# Schematic_Scout2Map_JSON.net
KiCad netlist of a schematic drawn in EasyEDA
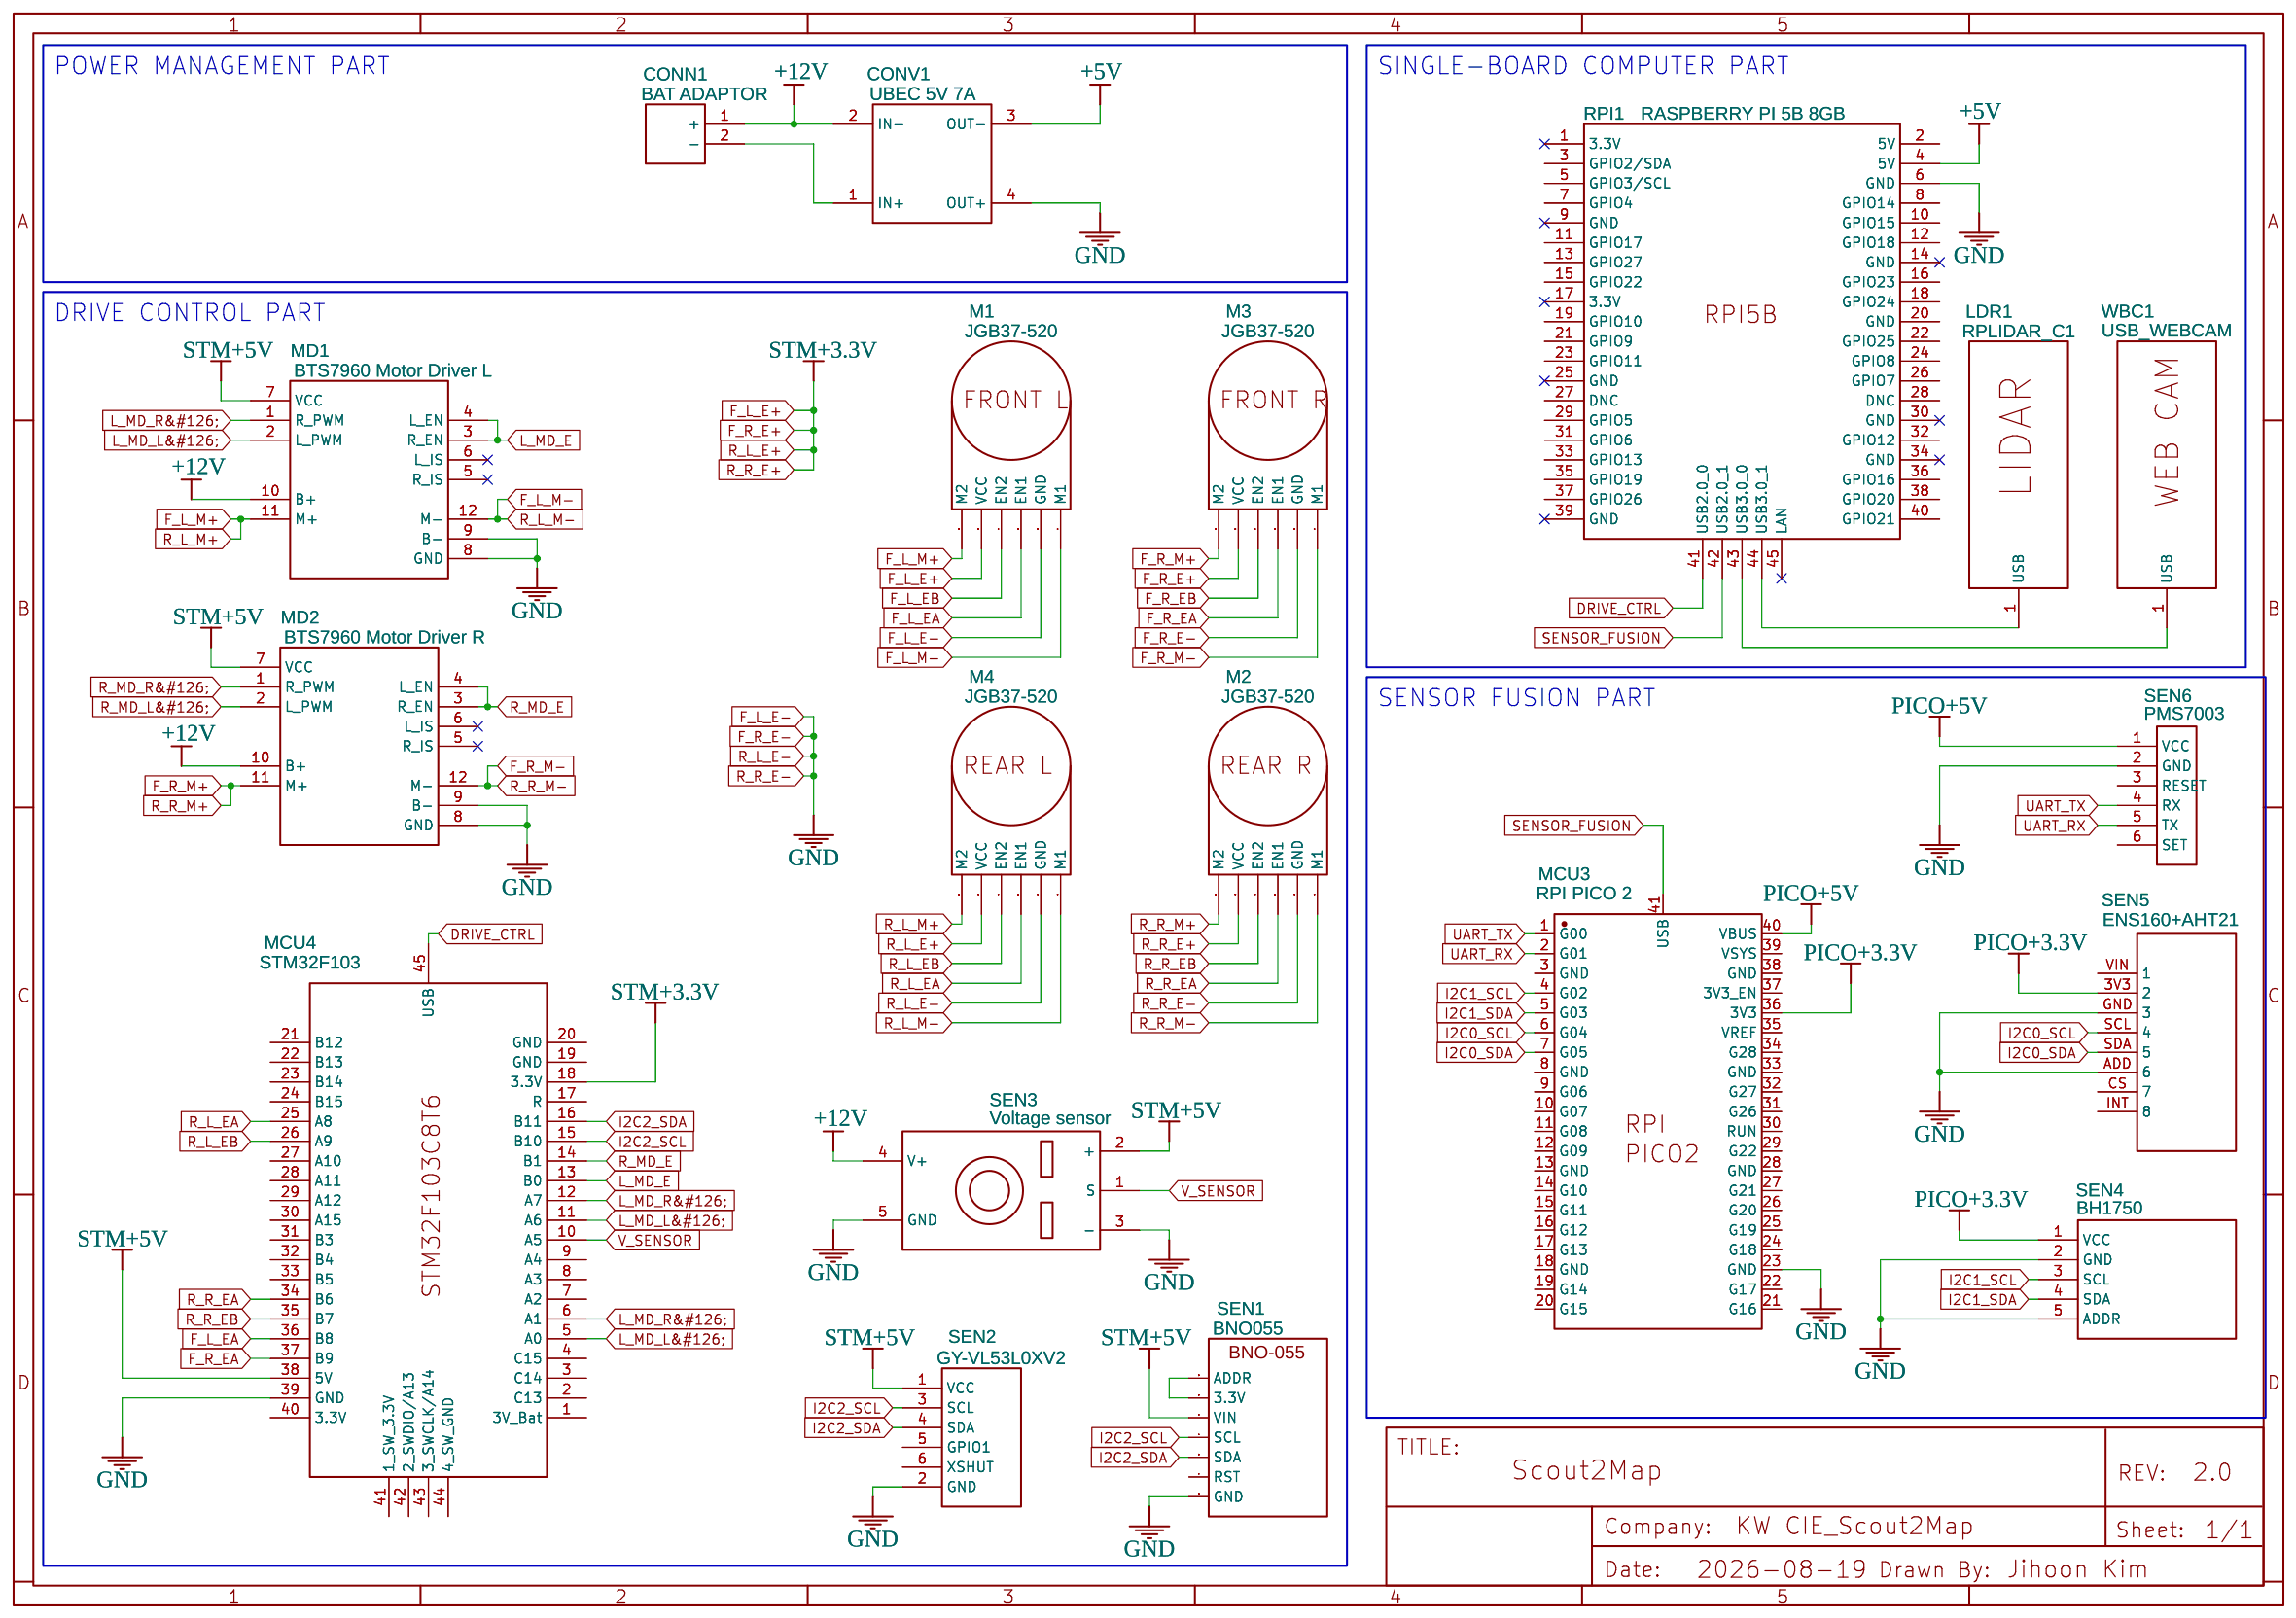
[diagram p0: schematic sheet]

(export (version "E")
  (design (tool "Eeschema 10.0.6"))
  (components
    (comp (ref "CONN1") (value "BAT ADAPTOR") (libsource (lib "") (part "Ac Adaptor")))
    (comp (ref "CONV1") (value "UBEC 5V 7A") (libsource (lib "") (part "Stepdown")))
    (comp (ref "LDR1") (value "RPLIDAR_C1") (libsource (lib "") (part "TFMini_Plus_Lidar_1")))
    (comp (ref "M1") (value "JGB37-520") (libsource (lib "") (part "N20_with_ENCODER_1")))
    (comp (ref "M2") (value "JGB37-520") (libsource (lib "") (part "N20_with_ENCODER_3")))
    (comp (ref "M3") (value "JGB37-520") (libsource (lib "") (part "N20_with_ENCODER")))
    (comp (ref "M4") (value "JGB37-520") (libsource (lib "") (part "N20_with_ENCODER_2")))
    (comp (ref "MCU3")
      (value "RPI PICO 2")
      (fields (field (name "Manufacturer Part") "SC0918") (field (name "Manufacturer") "Raspberry Pi"))
      (libsource (lib "") (part "RaspberryPi_Pico2 + USB"))
    )
    (comp (ref "MCU4")
      (value "STM32F103")
      (fields (field (name "Manufacturer Part") "STM32F103C8T6"))
      (libsource (lib "") (part "STM32F103C8T6 + USB"))
    )
    (comp (ref "MD1") (value "BTS7960 Motor Driver L") (libsource (lib "") (part "BST7960 Motor Drover")))
    (comp (ref "MD2") (value "BTS7960 Motor Driver R") (libsource (lib "") (part "BST7960 Motor Drover")))
    (comp (ref "RPI1")
      (value "RASPBERRY PI 5B 8GB")
      (fields
        (field (name "Manufacturer Part") "Raspberry Pi 4 Model B")
        (field (name "Manufacturer") "Raspberry Pi")
      )
      (libsource (lib "") (part "RASPBERRY PI 4B + USB"))
    )
    (comp (ref "SEN1") (value "BNO055") (libsource (lib "") (part "BNO055")))
    (comp (ref "SEN2") (value "GY-VL53L0XV2") (libsource (lib "") (part "GY-VL53L0XV2")))
    (comp (ref "SEN3") (value "Voltage sensor") (libsource (lib "") (part "Voltage sensor")))
    (comp (ref "SEN4") (value "BH1750") (libsource (lib "") (part "BH1750")))
    (comp (ref "SEN5") (value "ENS160+AHT21") (libsource (lib "") (part "ENS160+AHT21")))
    (comp (ref "SEN6") (value "PMS7003") (libsource (lib "") (part "Plantower PMS7003")))
    (comp (ref "WBC1") (value "USB_WEBCAM") (libsource (lib "") (part "TFMini_Plus_Lidar")))
  )
  (nets
    (net (code "1") (name "+5V") (class "Default")
      (node (ref "CONV1") (pin "3") (pinfunction "OUT-_3") (pintype "unspecified"))
      (node (ref "RPI1") (pin "4") (pinfunction "5V_4") (pintype "passive"))
    )
    (net (code "2") (name "+12V") (class "Default")
      (node (ref "CONN1") (pin "1") (pinfunction "+_1") (pintype "unspecified"))
      (node (ref "CONV1") (pin "2") (pinfunction "IN-_2") (pintype "unspecified"))
      (node (ref "MD1") (pin "10") (pinfunction "B+_10") (pintype "unspecified"))
      (node (ref "MD2") (pin "10") (pinfunction "B+_10") (pintype "unspecified"))
      (node (ref "SEN3") (pin "4") (pinfunction "V+_4") (pintype "unspecified"))
    )
    (net (code "3") (name "DRIVE_CTRL") (class "Default")
      (node (ref "MCU4") (pin "45") (pinfunction "USB_45") (pintype "unspecified"))
      (node (ref "RPI1") (pin "41") (pinfunction "USB2.0_0_41") (pintype "bidirectional"))
    )
    (net (code "4") (name "F_L_E+") (class "Default")
      (node (ref "M1") (pin "5") (pinfunction "VCC_5") (pintype "unspecified"))
      (node (ref "M2") (pin "5") (pinfunction "VCC_5") (pintype "unspecified"))
      (node (ref "M3") (pin "5") (pinfunction "VCC_5") (pintype "unspecified"))
      (node (ref "M4") (pin "5") (pinfunction "VCC_5") (pintype "unspecified"))
      (node (ref "MCU4") (pin "18") (pinfunction "3.3V_18") (pintype "unspecified"))
    )
    (net (code "5") (name "F_L_E-") (class "Default")
      (node (ref "CONV1") (pin "4") (pinfunction "OUT+_4") (pintype "unspecified"))
      (node (ref "M1") (pin "2") (pinfunction "GND_2") (pintype "unspecified"))
      (node (ref "M2") (pin "2") (pinfunction "GND_2") (pintype "unspecified"))
      (node (ref "M3") (pin "2") (pinfunction "GND_2") (pintype "unspecified"))
      (node (ref "M4") (pin "2") (pinfunction "GND_2") (pintype "unspecified"))
      (node (ref "MCU3") (pin "23") (pinfunction "GND_23") (pintype "unspecified"))
      (node (ref "MCU4") (pin "39") (pinfunction "GND_39") (pintype "unspecified"))
      (node (ref "MD1") (pin "8") (pinfunction "GND_8") (pintype "unspecified"))
      (node (ref "MD1") (pin "9") (pinfunction "B-_9") (pintype "unspecified"))
      (node (ref "MD2") (pin "8") (pinfunction "GND_8") (pintype "unspecified"))
      (node (ref "MD2") (pin "9") (pinfunction "B-_9") (pintype "unspecified"))
      (node (ref "RPI1") (pin "6") (pinfunction "GND_6") (pintype "unspecified"))
      (node (ref "SEN1") (pin "3") (pinfunction "GND_3") (pintype "unspecified"))
      (node (ref "SEN2") (pin "2") (pinfunction "GND_2") (pintype "unspecified"))
      (node (ref "SEN3") (pin "3") (pinfunction "-_3") (pintype "unspecified"))
      (node (ref "SEN3") (pin "5") (pinfunction "GND_5") (pintype "unspecified"))
      (node (ref "SEN4") (pin "2") (pinfunction "GND_2") (pintype "unspecified"))
      (node (ref "SEN4") (pin "5") (pinfunction "ADDR_5") (pintype "unspecified"))
      (node (ref "SEN5") (pin "ADD") (pinfunction "6_ADD") (pintype "unspecified"))
      (node (ref "SEN5") (pin "GND") (pinfunction "3_GND") (pintype "unspecified"))
      (node (ref "SEN6") (pin "2") (pinfunction "GND_2") (pintype "unspecified"))
    )
    (net (code "6") (name "F_L_EA") (class "Default")
      (node (ref "M1") (pin "3") (pinfunction "EN1_3") (pintype "unspecified"))
      (node (ref "MCU4") (pin "36") (pinfunction "B8_36") (pintype "unspecified"))
    )
    (net (code "7") (name "F_L_EB") (class "Default")
      (node (ref "M1") (pin "4") (pinfunction "EN2_4") (pintype "unspecified"))
    )
    (net (code "8") (name "F_L_M+") (class "Default")
      (node (ref "M1") (pin "6") (pinfunction "M2_6") (pintype "unspecified"))
      (node (ref "M4") (pin "6") (pinfunction "M2_6") (pintype "unspecified"))
      (node (ref "MD1") (pin "11") (pinfunction "M+_11") (pintype "unspecified"))
    )
    (net (code "9") (name "F_L_M-") (class "Default")
      (node (ref "M1") (pin "1") (pinfunction "M1_1") (pintype "unspecified"))
      (node (ref "M4") (pin "1") (pinfunction "M1_1") (pintype "unspecified"))
      (node (ref "MD1") (pin "12") (pinfunction "M-_12") (pintype "unspecified"))
    )
    (net (code "10") (name "F_R_EA") (class "Default")
      (node (ref "M3") (pin "3") (pinfunction "EN1_3") (pintype "unspecified"))
      (node (ref "MCU4") (pin "37") (pinfunction "B9_37") (pintype "unspecified"))
    )
    (net (code "11") (name "F_R_EB") (class "Default")
      (node (ref "M3") (pin "4") (pinfunction "EN2_4") (pintype "unspecified"))
    )
    (net (code "12") (name "F_R_M+") (class "Default")
      (node (ref "M2") (pin "6") (pinfunction "M2_6") (pintype "unspecified"))
      (node (ref "M3") (pin "6") (pinfunction "M2_6") (pintype "unspecified"))
      (node (ref "MD2") (pin "11") (pinfunction "M+_11") (pintype "unspecified"))
    )
    (net (code "13") (name "F_R_M-") (class "Default")
      (node (ref "M2") (pin "1") (pinfunction "M1_1") (pintype "unspecified"))
      (node (ref "M3") (pin "1") (pinfunction "M1_1") (pintype "unspecified"))
      (node (ref "MD2") (pin "12") (pinfunction "M-_12") (pintype "unspecified"))
    )
    (net (code "14") (name "I2C0_SCL") (class "Default")
      (node (ref "MCU3") (pin "6") (pinfunction "G04_6") (pintype "unspecified"))
      (node (ref "SEN5") (pin "SCL") (pinfunction "4_SCL") (pintype "unspecified"))
    )
    (net (code "15") (name "I2C0_SDA") (class "Default")
      (node (ref "MCU3") (pin "7") (pinfunction "G05_7") (pintype "unspecified"))
      (node (ref "SEN5") (pin "SDA") (pinfunction "5_SDA") (pintype "unspecified"))
    )
    (net (code "16") (name "I2C1_SCL") (class "Default")
      (node (ref "MCU3") (pin "4") (pinfunction "G02_4") (pintype "unspecified"))
      (node (ref "SEN4") (pin "3") (pinfunction "SCL_3") (pintype "unspecified"))
    )
    (net (code "17") (name "I2C1_SDA") (class "Default")
      (node (ref "MCU3") (pin "5") (pinfunction "G03_5") (pintype "unspecified"))
      (node (ref "SEN4") (pin "4") (pinfunction "SDA_4") (pintype "unspecified"))
    )
    (net (code "18") (name "I2C2_SCL") (class "Default")
      (node (ref "MCU4") (pin "15") (pinfunction "B10_15") (pintype "unspecified"))
      (node (ref "SEN1") (pin "4") (pinfunction "SCL_4") (pintype "unspecified"))
      (node (ref "SEN2") (pin "3") (pinfunction "SCL_3") (pintype "unspecified"))
    )
    (net (code "19") (name "I2C2_SDA") (class "Default")
      (node (ref "MCU4") (pin "16") (pinfunction "B11_16") (pintype "unspecified"))
      (node (ref "SEN1") (pin "5") (pinfunction "SDA_5") (pintype "unspecified"))
      (node (ref "SEN2") (pin "4") (pinfunction "SDA_4") (pintype "unspecified"))
    )
    (net (code "20") (name "L_MD_E") (class "Default")
      (node (ref "MCU4") (pin "13") (pinfunction "B0_13") (pintype "unspecified"))
      (node (ref "MD1") (pin "3") (pinfunction "R_EN_3") (pintype "unspecified"))
      (node (ref "MD1") (pin "4") (pinfunction "L_EN_4") (pintype "unspecified"))
    )
    (net (code "21") (name "L_MD_L&#126;") (class "Default")
      (node (ref "MCU4") (pin "11") (pinfunction "A6_11") (pintype "unspecified"))
      (node (ref "MCU4") (pin "5") (pinfunction "A0_5") (pintype "unspecified"))
      (node (ref "MD1") (pin "2") (pinfunction "L_PWM_2") (pintype "unspecified"))
    )
    (net (code "22") (name "L_MD_R&#126;") (class "Default")
      (node (ref "MCU4") (pin "12") (pinfunction "A7_12") (pintype "unspecified"))
      (node (ref "MCU4") (pin "6") (pinfunction "A1_6") (pintype "unspecified"))
      (node (ref "MD1") (pin "1") (pinfunction "R_PWM_1") (pintype "unspecified"))
    )
    (net (code "23") (name "Net-(CONN1--)") (class "Default")
      (node (ref "CONN1") (pin "2") (pinfunction "-_2") (pintype "unspecified"))
      (node (ref "CONV1") (pin "1") (pinfunction "IN+_1") (pintype "unspecified"))
    )
    (net (code "24") (name "Net-(LDR1-USB)") (class "Default")
      (node (ref "LDR1") (pin "1") (pinfunction "USB_1") (pintype "unspecified"))
      (node (ref "RPI1") (pin "44") (pinfunction "USB3.0_1_44") (pintype "bidirectional"))
    )
    (net (code "25") (name "Net-(RPI1-USB3.0_0)") (class "Default")
      (node (ref "RPI1") (pin "43") (pinfunction "USB3.0_0_43") (pintype "bidirectional"))
      (node (ref "WBC1") (pin "1") (pinfunction "USB_1") (pintype "unspecified"))
    )
    (net (code "26") (name "Net-(SEN1-3.3V)") (class "Default")
      (node (ref "SEN1") (pin "2") (pinfunction "3.3V_2") (pintype "unspecified"))
      (node (ref "SEN1") (pin "6") (pinfunction "ADDR_6") (pintype "unspecified"))
    )
    (net (code "27") (name "PICO+3.3V") (class "Default")
      (node (ref "MCU3") (pin "36") (pinfunction "3V3_36") (pintype "unspecified"))
      (node (ref "SEN4") (pin "1") (pinfunction "VCC_1") (pintype "unspecified"))
      (node (ref "SEN5") (pin "3V3") (pinfunction "2_3V3") (pintype "unspecified"))
    )
    (net (code "28") (name "PICO+5V") (class "Default")
      (node (ref "MCU3") (pin "40") (pinfunction "VBUS_40") (pintype "unspecified"))
      (node (ref "SEN6") (pin "1") (pinfunction "VCC_1") (pintype "unspecified"))
    )
    (net (code "29") (name "R_L_EA") (class "Default")
      (node (ref "M4") (pin "3") (pinfunction "EN1_3") (pintype "unspecified"))
      (node (ref "MCU4") (pin "25") (pinfunction "A8_25") (pintype "unspecified"))
    )
    (net (code "30") (name "R_L_EB") (class "Default")
      (node (ref "M4") (pin "4") (pinfunction "EN2_4") (pintype "unspecified"))
      (node (ref "MCU4") (pin "26") (pinfunction "A9_26") (pintype "unspecified"))
    )
    (net (code "31") (name "R_MD_E") (class "Default")
      (node (ref "MCU4") (pin "14") (pinfunction "B1_14") (pintype "unspecified"))
      (node (ref "MD2") (pin "3") (pinfunction "R_EN_3") (pintype "unspecified"))
      (node (ref "MD2") (pin "4") (pinfunction "L_EN_4") (pintype "unspecified"))
    )
    (net (code "32") (name "R_MD_L&#126;") (class "Default")
      (node (ref "MD2") (pin "2") (pinfunction "L_PWM_2") (pintype "unspecified"))
    )
    (net (code "33") (name "R_MD_R&#126;") (class "Default")
      (node (ref "MD2") (pin "1") (pinfunction "R_PWM_1") (pintype "unspecified"))
    )
    (net (code "34") (name "R_R_EA") (class "Default")
      (node (ref "M2") (pin "3") (pinfunction "EN1_3") (pintype "unspecified"))
      (node (ref "MCU4") (pin "34") (pinfunction "B6_34") (pintype "unspecified"))
    )
    (net (code "35") (name "R_R_EB") (class "Default")
      (node (ref "M2") (pin "4") (pinfunction "EN2_4") (pintype "unspecified"))
      (node (ref "MCU4") (pin "35") (pinfunction "B7_35") (pintype "unspecified"))
    )
    (net (code "36") (name "SENSOR_FUSION") (class "Default")
      (node (ref "MCU3") (pin "41") (pinfunction "USB_41") (pintype "unspecified"))
      (node (ref "RPI1") (pin "42") (pinfunction "USB2.0_1_42") (pintype "bidirectional"))
    )
    (net (code "37") (name "STM+5V") (class "Default")
      (node (ref "MCU4") (pin "38") (pinfunction "5V_38") (pintype "unspecified"))
      (node (ref "MD1") (pin "7") (pinfunction "VCC_7") (pintype "unspecified"))
      (node (ref "MD2") (pin "7") (pinfunction "VCC_7") (pintype "unspecified"))
      (node (ref "SEN1") (pin "1") (pinfunction "VIN_1") (pintype "unspecified"))
      (node (ref "SEN2") (pin "1") (pinfunction "VCC_1") (pintype "unspecified"))
      (node (ref "SEN3") (pin "2") (pinfunction "+_2") (pintype "unspecified"))
    )
    (net (code "38") (name "UART_RX") (class "Default")
      (node (ref "MCU3") (pin "2") (pinfunction "G01_2") (pintype "unspecified"))
      (node (ref "SEN6") (pin "5") (pinfunction "TX_5") (pintype "unspecified"))
    )
    (net (code "39") (name "UART_TX") (class "Default")
      (node (ref "MCU3") (pin "1") (pinfunction "G00_1") (pintype "unspecified"))
      (node (ref "SEN6") (pin "4") (pinfunction "RX_4") (pintype "unspecified"))
    )
    (net (code "40") (name "V_SENSOR") (class "Default")
      (node (ref "MCU4") (pin "10") (pinfunction "A5_10") (pintype "unspecified"))
      (node (ref "SEN3") (pin "1") (pinfunction "S_1") (pintype "unspecified"))
    )
    (net (code "41") (name "unconnected-(MCU3-3V3_EN-Pad37)") (class "Default")
      (node (ref "MCU3") (pin "37") (pinfunction "3V3_EN_37") (pintype "unspecified"))
    )
    (net (code "42") (name "unconnected-(MCU3-G06-Pad9)") (class "Default")
      (node (ref "MCU3") (pin "9") (pinfunction "G06_9") (pintype "unspecified"))
    )
    (net (code "43") (name "unconnected-(MCU3-G07-Pad10)") (class "Default")
      (node (ref "MCU3") (pin "10") (pinfunction "G07_10") (pintype "unspecified"))
    )
    (net (code "44") (name "unconnected-(MCU3-G08-Pad11)") (class "Default")
      (node (ref "MCU3") (pin "11") (pinfunction "G08_11") (pintype "unspecified"))
    )
    (net (code "45") (name "unconnected-(MCU3-G09-Pad12)") (class "Default")
      (node (ref "MCU3") (pin "12") (pinfunction "G09_12") (pintype "unspecified"))
    )
    (net (code "46") (name "unconnected-(MCU3-G10-Pad14)") (class "Default")
      (node (ref "MCU3") (pin "14") (pinfunction "G10_14") (pintype "unspecified"))
    )
    (net (code "47") (name "unconnected-(MCU3-G11-Pad15)") (class "Default")
      (node (ref "MCU3") (pin "15") (pinfunction "G11_15") (pintype "unspecified"))
    )
    (net (code "48") (name "unconnected-(MCU3-G12-Pad16)") (class "Default")
      (node (ref "MCU3") (pin "16") (pinfunction "G12_16") (pintype "unspecified"))
    )
    (net (code "49") (name "unconnected-(MCU3-G13-Pad17)") (class "Default")
      (node (ref "MCU3") (pin "17") (pinfunction "G13_17") (pintype "unspecified"))
    )
    (net (code "50") (name "unconnected-(MCU3-G14-Pad19)") (class "Default")
      (node (ref "MCU3") (pin "19") (pinfunction "G14_19") (pintype "unspecified"))
    )
    (net (code "51") (name "unconnected-(MCU3-G15-Pad20)") (class "Default")
      (node (ref "MCU3") (pin "20") (pinfunction "G15_20") (pintype "unspecified"))
    )
    (net (code "52") (name "unconnected-(MCU3-G16-Pad21)") (class "Default")
      (node (ref "MCU3") (pin "21") (pinfunction "G16_21") (pintype "unspecified"))
    )
    (net (code "53") (name "unconnected-(MCU3-G17-Pad22)") (class "Default")
      (node (ref "MCU3") (pin "22") (pinfunction "G17_22") (pintype "unspecified"))
    )
    (net (code "54") (name "unconnected-(MCU3-G18-Pad24)") (class "Default")
      (node (ref "MCU3") (pin "24") (pinfunction "G18_24") (pintype "unspecified"))
    )
    (net (code "55") (name "unconnected-(MCU3-G19-Pad25)") (class "Default")
      (node (ref "MCU3") (pin "25") (pinfunction "G19_25") (pintype "unspecified"))
    )
    (net (code "56") (name "unconnected-(MCU3-G20-Pad26)") (class "Default")
      (node (ref "MCU3") (pin "26") (pinfunction "G20_26") (pintype "unspecified"))
    )
    (net (code "57") (name "unconnected-(MCU3-G21-Pad27)") (class "Default")
      (node (ref "MCU3") (pin "27") (pinfunction "G21_27") (pintype "unspecified"))
    )
    (net (code "58") (name "unconnected-(MCU3-G22-Pad29)") (class "Default")
      (node (ref "MCU3") (pin "29") (pinfunction "G22_29") (pintype "unspecified"))
    )
    (net (code "59") (name "unconnected-(MCU3-G26-Pad31)") (class "Default")
      (node (ref "MCU3") (pin "31") (pinfunction "G26_31") (pintype "unspecified"))
    )
    (net (code "60") (name "unconnected-(MCU3-G27-Pad32)") (class "Default")
      (node (ref "MCU3") (pin "32") (pinfunction "G27_32") (pintype "unspecified"))
    )
    (net (code "61") (name "unconnected-(MCU3-G28-Pad34)") (class "Default")
      (node (ref "MCU3") (pin "34") (pinfunction "G28_34") (pintype "unspecified"))
    )
    (net (code "62") (name "unconnected-(MCU3-GND-Pad3)") (class "Default")
      (node (ref "MCU3") (pin "3") (pinfunction "GND_3") (pintype "unspecified"))
    )
    (net (code "63") (name "unconnected-(MCU3-GND-Pad8)") (class "Default")
      (node (ref "MCU3") (pin "8") (pinfunction "GND_8") (pintype "unspecified"))
    )
    (net (code "64") (name "unconnected-(MCU3-GND-Pad13)") (class "Default")
      (node (ref "MCU3") (pin "13") (pinfunction "GND_13") (pintype "unspecified"))
    )
    (net (code "65") (name "unconnected-(MCU3-GND-Pad18)") (class "Default")
      (node (ref "MCU3") (pin "18") (pinfunction "GND_18") (pintype "unspecified"))
    )
    (net (code "66") (name "unconnected-(MCU3-GND-Pad28)") (class "Default")
      (node (ref "MCU3") (pin "28") (pinfunction "GND_28") (pintype "unspecified"))
    )
    (net (code "67") (name "unconnected-(MCU3-GND-Pad33)") (class "Default")
      (node (ref "MCU3") (pin "33") (pinfunction "GND_33") (pintype "unspecified"))
    )
    (net (code "68") (name "unconnected-(MCU3-GND-Pad38)") (class "Default")
      (node (ref "MCU3") (pin "38") (pinfunction "GND_38") (pintype "unspecified"))
    )
    (net (code "69") (name "unconnected-(MCU3-RUN-Pad30)") (class "Default")
      (node (ref "MCU3") (pin "30") (pinfunction "RUN_30") (pintype "unspecified"))
    )
    (net (code "70") (name "unconnected-(MCU3-VREF-Pad35)") (class "Default")
      (node (ref "MCU3") (pin "35") (pinfunction "VREF_35") (pintype "unspecified"))
    )
    (net (code "71") (name "unconnected-(MCU3-VSYS-Pad39)") (class "Default")
      (node (ref "MCU3") (pin "39") (pinfunction "VSYS_39") (pintype "unspecified"))
    )
    (net (code "72") (name "unconnected-(MCU4-1_SW_3.3V-Pad41)") (class "Default")
      (node (ref "MCU4") (pin "41") (pinfunction "1_SW_3.3V_41") (pintype "unspecified"))
    )
    (net (code "73") (name "unconnected-(MCU4-2_SWDIO{slash}A13-Pad42)") (class "Default")
      (node (ref "MCU4") (pin "42") (pinfunction "2_SWDIO/A13_42") (pintype "unspecified"))
    )
    (net (code "74") (name "unconnected-(MCU4-3.3V-Pad40)") (class "Default")
      (node (ref "MCU4") (pin "40") (pinfunction "3.3V_40") (pintype "unspecified"))
    )
    (net (code "75") (name "unconnected-(MCU4-3V_Bat-Pad1)") (class "Default")
      (node (ref "MCU4") (pin "1") (pinfunction "3V_Bat_1") (pintype "unspecified"))
    )
    (net (code "76") (name "unconnected-(MCU4-3_SWCLK{slash}A14-Pad43)") (class "Default")
      (node (ref "MCU4") (pin "43") (pinfunction "3_SWCLK/A14_43") (pintype "unspecified"))
    )
    (net (code "77") (name "unconnected-(MCU4-4_SW_GND-Pad44)") (class "Default")
      (node (ref "MCU4") (pin "44") (pinfunction "4_SW_GND_44") (pintype "unspecified"))
    )
    (net (code "78") (name "unconnected-(MCU4-A2-Pad7)") (class "Default")
      (node (ref "MCU4") (pin "7") (pinfunction "A2_7") (pintype "unspecified"))
    )
    (net (code "79") (name "unconnected-(MCU4-A3-Pad8)") (class "Default")
      (node (ref "MCU4") (pin "8") (pinfunction "A3_8") (pintype "unspecified"))
    )
    (net (code "80") (name "unconnected-(MCU4-A4-Pad9)") (class "Default")
      (node (ref "MCU4") (pin "9") (pinfunction "A4_9") (pintype "unspecified"))
    )
    (net (code "81") (name "unconnected-(MCU4-A10-Pad27)") (class "Default")
      (node (ref "MCU4") (pin "27") (pinfunction "A10_27") (pintype "unspecified"))
    )
    (net (code "82") (name "unconnected-(MCU4-A11-Pad28)") (class "Default")
      (node (ref "MCU4") (pin "28") (pinfunction "A11_28") (pintype "unspecified"))
    )
    (net (code "83") (name "unconnected-(MCU4-A12-Pad29)") (class "Default")
      (node (ref "MCU4") (pin "29") (pinfunction "A12_29") (pintype "unspecified"))
    )
    (net (code "84") (name "unconnected-(MCU4-A15-Pad30)") (class "Default")
      (node (ref "MCU4") (pin "30") (pinfunction "A15_30") (pintype "unspecified"))
    )
    (net (code "85") (name "unconnected-(MCU4-B3-Pad31)") (class "Default")
      (node (ref "MCU4") (pin "31") (pinfunction "B3_31") (pintype "unspecified"))
    )
    (net (code "86") (name "unconnected-(MCU4-B4-Pad32)") (class "Default")
      (node (ref "MCU4") (pin "32") (pinfunction "B4_32") (pintype "unspecified"))
    )
    (net (code "87") (name "unconnected-(MCU4-B5-Pad33)") (class "Default")
      (node (ref "MCU4") (pin "33") (pinfunction "B5_33") (pintype "unspecified"))
    )
    (net (code "88") (name "unconnected-(MCU4-B12-Pad21)") (class "Default")
      (node (ref "MCU4") (pin "21") (pinfunction "B12_21") (pintype "bidirectional"))
    )
    (net (code "89") (name "unconnected-(MCU4-B13-Pad22)") (class "Default")
      (node (ref "MCU4") (pin "22") (pinfunction "B13_22") (pintype "bidirectional"))
    )
    (net (code "90") (name "unconnected-(MCU4-B14-Pad23)") (class "Default")
      (node (ref "MCU4") (pin "23") (pinfunction "B14_23") (pintype "bidirectional"))
    )
    (net (code "91") (name "unconnected-(MCU4-B15-Pad24)") (class "Default")
      (node (ref "MCU4") (pin "24") (pinfunction "B15_24") (pintype "bidirectional"))
    )
    (net (code "92") (name "unconnected-(MCU4-C13-Pad2)") (class "Default")
      (node (ref "MCU4") (pin "2") (pinfunction "C13_2") (pintype "unspecified"))
    )
    (net (code "93") (name "unconnected-(MCU4-C14-Pad3)") (class "Default")
      (node (ref "MCU4") (pin "3") (pinfunction "C14_3") (pintype "unspecified"))
    )
    (net (code "94") (name "unconnected-(MCU4-C15-Pad4)") (class "Default")
      (node (ref "MCU4") (pin "4") (pinfunction "C15_4") (pintype "unspecified"))
    )
    (net (code "95") (name "unconnected-(MCU4-GND-Pad19)") (class "Default")
      (node (ref "MCU4") (pin "19") (pinfunction "GND_19") (pintype "unspecified"))
    )
    (net (code "96") (name "unconnected-(MCU4-GND-Pad20)") (class "Default")
      (node (ref "MCU4") (pin "20") (pinfunction "GND_20") (pintype "unspecified"))
    )
    (net (code "97") (name "unconnected-(MCU4-R-Pad17)") (class "Default")
      (node (ref "MCU4") (pin "17") (pinfunction "R_17") (pintype "unspecified"))
    )
    (net (code "98") (name "unconnected-(MD1-L_IS-Pad6)") (class "Default")
      (node (ref "MD1") (pin "6") (pinfunction "L_IS_6") (pintype "unspecified+no_connect"))
    )
    (net (code "99") (name "unconnected-(MD1-R_IS-Pad5)") (class "Default")
      (node (ref "MD1") (pin "5") (pinfunction "R_IS_5") (pintype "unspecified+no_connect"))
    )
    (net (code "100") (name "unconnected-(MD2-L_IS-Pad6)") (class "Default")
      (node (ref "MD2") (pin "6") (pinfunction "L_IS_6") (pintype "unspecified+no_connect"))
    )
    (net (code "101") (name "unconnected-(MD2-R_IS-Pad5)") (class "Default")
      (node (ref "MD2") (pin "5") (pinfunction "R_IS_5") (pintype "unspecified+no_connect"))
    )
    (net (code "102") (name "unconnected-(RPI1-3.3V-Pad1)") (class "Default")
      (node (ref "RPI1") (pin "1") (pinfunction "3.3V_1") (pintype "passive+no_connect"))
    )
    (net (code "103") (name "unconnected-(RPI1-3.3V-Pad17)") (class "Default")
      (node (ref "RPI1") (pin "17") (pinfunction "3.3V_17") (pintype "passive+no_connect"))
    )
    (net (code "104") (name "unconnected-(RPI1-5V-Pad2)") (class "Default")
      (node (ref "RPI1") (pin "2") (pinfunction "5V_2") (pintype "passive"))
    )
    (net (code "105") (name "unconnected-(RPI1-DNC-Pad27)") (class "Default")
      (node (ref "RPI1") (pin "27") (pinfunction "DNC_27") (pintype "unspecified"))
    )
    (net (code "106") (name "unconnected-(RPI1-DNC-Pad28)") (class "Default")
      (node (ref "RPI1") (pin "28") (pinfunction "DNC_28") (pintype "unspecified"))
    )
    (net (code "107") (name "unconnected-(RPI1-GND-Pad9)") (class "Default")
      (node (ref "RPI1") (pin "9") (pinfunction "GND_9") (pintype "unspecified+no_connect"))
    )
    (net (code "108") (name "unconnected-(RPI1-GND-Pad14)") (class "Default")
      (node (ref "RPI1") (pin "14") (pinfunction "GND_14") (pintype "unspecified+no_connect"))
    )
    (net (code "109") (name "unconnected-(RPI1-GND-Pad20)") (class "Default")
      (node (ref "RPI1") (pin "20") (pinfunction "GND_20") (pintype "unspecified"))
    )
    (net (code "110") (name "unconnected-(RPI1-GND-Pad25)") (class "Default")
      (node (ref "RPI1") (pin "25") (pinfunction "GND_25") (pintype "unspecified+no_connect"))
    )
    (net (code "111") (name "unconnected-(RPI1-GND-Pad30)") (class "Default")
      (node (ref "RPI1") (pin "30") (pinfunction "GND_30") (pintype "unspecified+no_connect"))
    )
    (net (code "112") (name "unconnected-(RPI1-GND-Pad34)") (class "Default")
      (node (ref "RPI1") (pin "34") (pinfunction "GND_34") (pintype "unspecified+no_connect"))
    )
    (net (code "113") (name "unconnected-(RPI1-GND-Pad39)") (class "Default")
      (node (ref "RPI1") (pin "39") (pinfunction "GND_39") (pintype "unspecified+no_connect"))
    )
    (net (code "114") (name "unconnected-(RPI1-GPIO2{slash}SDA-Pad3)") (class "Default")
      (node (ref "RPI1") (pin "3") (pinfunction "GPIO2/SDA_3") (pintype "bidirectional"))
    )
    (net (code "115") (name "unconnected-(RPI1-GPIO3{slash}SCL-Pad5)") (class "Default")
      (node (ref "RPI1") (pin "5") (pinfunction "GPIO3/SCL_5") (pintype "bidirectional"))
    )
    (net (code "116") (name "unconnected-(RPI1-GPIO4-Pad7)") (class "Default")
      (node (ref "RPI1") (pin "7") (pinfunction "GPIO4_7") (pintype "bidirectional"))
    )
    (net (code "117") (name "unconnected-(RPI1-GPIO5-Pad29)") (class "Default")
      (node (ref "RPI1") (pin "29") (pinfunction "GPIO5_29") (pintype "bidirectional"))
    )
    (net (code "118") (name "unconnected-(RPI1-GPIO6-Pad31)") (class "Default")
      (node (ref "RPI1") (pin "31") (pinfunction "GPIO6_31") (pintype "bidirectional"))
    )
    (net (code "119") (name "unconnected-(RPI1-GPIO7-Pad26)") (class "Default")
      (node (ref "RPI1") (pin "26") (pinfunction "GPIO7_26") (pintype "bidirectional"))
    )
    (net (code "120") (name "unconnected-(RPI1-GPIO8-Pad24)") (class "Default")
      (node (ref "RPI1") (pin "24") (pinfunction "GPIO8_24") (pintype "bidirectional"))
    )
    (net (code "121") (name "unconnected-(RPI1-GPIO9-Pad21)") (class "Default")
      (node (ref "RPI1") (pin "21") (pinfunction "GPIO9_21") (pintype "bidirectional"))
    )
    (net (code "122") (name "unconnected-(RPI1-GPIO10-Pad19)") (class "Default")
      (node (ref "RPI1") (pin "19") (pinfunction "GPIO10_19") (pintype "bidirectional"))
    )
    (net (code "123") (name "unconnected-(RPI1-GPIO11-Pad23)") (class "Default")
      (node (ref "RPI1") (pin "23") (pinfunction "GPIO11_23") (pintype "bidirectional"))
    )
    (net (code "124") (name "unconnected-(RPI1-GPIO12-Pad32)") (class "Default")
      (node (ref "RPI1") (pin "32") (pinfunction "GPIO12_32") (pintype "bidirectional"))
    )
    (net (code "125") (name "unconnected-(RPI1-GPIO13-Pad33)") (class "Default")
      (node (ref "RPI1") (pin "33") (pinfunction "GPIO13_33") (pintype "bidirectional"))
    )
    (net (code "126") (name "unconnected-(RPI1-GPIO14-Pad8)") (class "Default")
      (node (ref "RPI1") (pin "8") (pinfunction "GPIO14_8") (pintype "bidirectional"))
    )
    (net (code "127") (name "unconnected-(RPI1-GPIO15-Pad10)") (class "Default")
      (node (ref "RPI1") (pin "10") (pinfunction "GPIO15_10") (pintype "bidirectional"))
    )
    (net (code "128") (name "unconnected-(RPI1-GPIO16-Pad36)") (class "Default")
      (node (ref "RPI1") (pin "36") (pinfunction "GPIO16_36") (pintype "bidirectional"))
    )
    (net (code "129") (name "unconnected-(RPI1-GPIO17-Pad11)") (class "Default")
      (node (ref "RPI1") (pin "11") (pinfunction "GPIO17_11") (pintype "bidirectional"))
    )
    (net (code "130") (name "unconnected-(RPI1-GPIO18-Pad12)") (class "Default")
      (node (ref "RPI1") (pin "12") (pinfunction "GPIO18_12") (pintype "bidirectional"))
    )
    (net (code "131") (name "unconnected-(RPI1-GPIO19-Pad35)") (class "Default")
      (node (ref "RPI1") (pin "35") (pinfunction "GPIO19_35") (pintype "bidirectional"))
    )
    (net (code "132") (name "unconnected-(RPI1-GPIO20-Pad38)") (class "Default")
      (node (ref "RPI1") (pin "38") (pinfunction "GPIO20_38") (pintype "bidirectional"))
    )
    (net (code "133") (name "unconnected-(RPI1-GPIO21-Pad40)") (class "Default")
      (node (ref "RPI1") (pin "40") (pinfunction "GPIO21_40") (pintype "bidirectional"))
    )
    (net (code "134") (name "unconnected-(RPI1-GPIO22-Pad15)") (class "Default")
      (node (ref "RPI1") (pin "15") (pinfunction "GPIO22_15") (pintype "bidirectional"))
    )
    (net (code "135") (name "unconnected-(RPI1-GPIO23-Pad16)") (class "Default")
      (node (ref "RPI1") (pin "16") (pinfunction "GPIO23_16") (pintype "bidirectional"))
    )
    (net (code "136") (name "unconnected-(RPI1-GPIO24-Pad18)") (class "Default")
      (node (ref "RPI1") (pin "18") (pinfunction "GPIO24_18") (pintype "bidirectional"))
    )
    (net (code "137") (name "unconnected-(RPI1-GPIO25-Pad22)") (class "Default")
      (node (ref "RPI1") (pin "22") (pinfunction "GPIO25_22") (pintype "bidirectional"))
    )
    (net (code "138") (name "unconnected-(RPI1-GPIO26-Pad37)") (class "Default")
      (node (ref "RPI1") (pin "37") (pinfunction "GPIO26_37") (pintype "bidirectional"))
    )
    (net (code "139") (name "unconnected-(RPI1-GPIO27-Pad13)") (class "Default")
      (node (ref "RPI1") (pin "13") (pinfunction "GPIO27_13") (pintype "bidirectional"))
    )
    (net (code "140") (name "unconnected-(RPI1-LAN-Pad45)") (class "Default")
      (node (ref "RPI1") (pin "45") (pinfunction "LAN_45") (pintype "bidirectional+no_connect"))
    )
    (net (code "141") (name "unconnected-(SEN1-RST-Pad7)") (class "Default")
      (node (ref "SEN1") (pin "7") (pinfunction "RST_7") (pintype "unspecified"))
    )
    (net (code "142") (name "unconnected-(SEN2-GPIO1-Pad5)") (class "Default")
      (node (ref "SEN2") (pin "5") (pinfunction "GPIO1_5") (pintype "unspecified"))
    )
    (net (code "143") (name "unconnected-(SEN2-XSHUT-Pad6)") (class "Default")
      (node (ref "SEN2") (pin "6") (pinfunction "XSHUT_6") (pintype "unspecified"))
    )
    (net (code "144") (name "unconnected-(SEN5-1-PadVIN)") (class "Default")
      (node (ref "SEN5") (pin "VIN") (pinfunction "1_VIN") (pintype "unspecified"))
    )
    (net (code "145") (name "unconnected-(SEN5-7-PadCS)") (class "Default")
      (node (ref "SEN5") (pin "CS") (pinfunction "7_CS") (pintype "unspecified"))
    )
    (net (code "146") (name "unconnected-(SEN5-8-PadINT)") (class "Default")
      (node (ref "SEN5") (pin "INT") (pinfunction "8_INT") (pintype "unspecified"))
    )
    (net (code "147") (name "unconnected-(SEN6-RESET-Pad3)") (class "Default")
      (node (ref "SEN6") (pin "3") (pinfunction "RESET_3") (pintype "unspecified"))
    )
    (net (code "148") (name "unconnected-(SEN6-SET-Pad6)") (class "Default")
      (node (ref "SEN6") (pin "6") (pinfunction "SET_6") (pintype "unspecified"))
    )
  )
)
